# main.net
KiCad netlist of a schematic drawn in Altium Designer
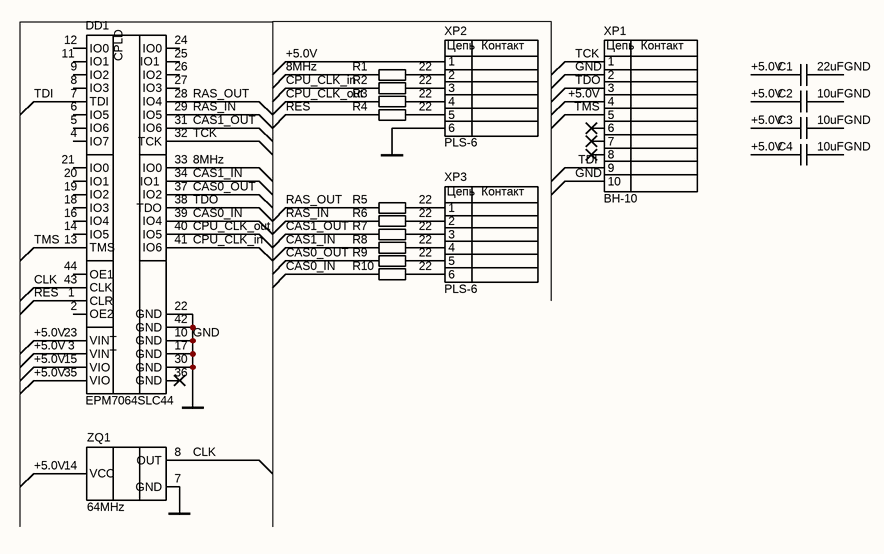
[diagram p0: main.SchDoc]

(export (version "E")
  (design (tool "Eeschema 10.0.6"))
  (components
    (comp (ref "C1") (value "22uF") (footprint "С1206") (libsource (lib "Capacitors") (part "CapCer")))
    (comp (ref "C2") (value "10uF") (footprint "C0805") (libsource (lib "Capacitors") (part "CapCer")))
    (comp (ref "C3") (value "10uF") (footprint "C0805") (libsource (lib "Capacitors") (part "CapCer")))
    (comp (ref "C4") (value "10uF") (footprint "C0805") (libsource (lib "Capacitors") (part "CapCer")))
    (comp (ref "DD1")
      (value "EPM7064SLC44")
      (footprint "PLCC-44-R")
      (description "44-Pin PLCC44")
      (libsource (lib "cpld") (part "EPM7064SLC44"))
    )
    (comp (ref "R1")
      (value "22")
      (footprint "R0603")
      (description "22 Ом 0603")
      (libsource (lib "Resistors") (part "Res"))
    )
    (comp (ref "R2")
      (value "22")
      (footprint "R0603")
      (description "22 Ом 0603")
      (libsource (lib "Resistors") (part "Res"))
    )
    (comp (ref "R3")
      (value "22")
      (footprint "R0603")
      (description "22 Ом 0603")
      (libsource (lib "Resistors") (part "Res"))
    )
    (comp (ref "R4")
      (value "22")
      (footprint "R0603")
      (description "22 Ом 0603")
      (libsource (lib "Resistors") (part "Res"))
    )
    (comp (ref "R5")
      (value "22")
      (footprint "R0603")
      (description "22 Ом 0603")
      (libsource (lib "Resistors") (part "Res"))
    )
    (comp (ref "R6")
      (value "22")
      (footprint "R0603")
      (description "22 Ом 0603")
      (libsource (lib "Resistors") (part "Res"))
    )
    (comp (ref "R7")
      (value "22")
      (footprint "R0603")
      (description "22 Ом 0603")
      (libsource (lib "Resistors") (part "Res"))
    )
    (comp (ref "R8")
      (value "22")
      (footprint "R0603")
      (description "22 Ом 0603")
      (libsource (lib "Resistors") (part "Res"))
    )
    (comp (ref "R9")
      (value "22")
      (footprint "R0603")
      (description "22 Ом 0603")
      (libsource (lib "Resistors") (part "Res"))
    )
    (comp (ref "R10")
      (value "22")
      (footprint "R0603")
      (description "22 Ом 0603")
      (libsource (lib "Resistors") (part "Res"))
    )
    (comp (ref "XP1")
      (value "BH-10")
      (footprint "BH-10")
      (description "10 Position Total Dual Row 2.54 mm Pitch Straight Male Shrouded Box Header")
      (fields (field (name "MF") "Sullins Connector") (field (name "MP") "SBH11-PBPC-D05-ST-BK"))
      (libsource (lib "Connectors") (part "BH-10"))
    )
    (comp (ref "XP2") (value "PLS-6") (footprint "6pin") (libsource (lib "Connectors") (part "PLS-6")))
    (comp (ref "XP3") (value "PLS-6") (footprint "6pin") (libsource (lib "Connectors") (part "PLS-6")))
    (comp (ref "ZQ1")
      (value "64MHz")
      (footprint "OSC_ECS-100A-240")
      (description "Oscillator  14-DIP, 4 Leads (Full Size, Metal Can)")
      (fields (field (name "MP") "ECS-100A-240"))
      (libsource (lib "Oscillators") (part "KXO-240"))
    )
  )
  (nets
    (net (code "1") (name "/+5.0V") (class "Default")
      (node (ref "C1") (pin "1") (pinfunction "1_1") (pintype "passive"))
      (node (ref "C2") (pin "1") (pinfunction "1_1") (pintype "passive"))
      (node (ref "C3") (pin "1") (pinfunction "1_1") (pintype "passive"))
      (node (ref "C4") (pin "1") (pinfunction "1_1") (pintype "passive"))
      (node (ref "DD1") (pin "15") (pinfunction "VIO_15") (pintype "passive"))
      (node (ref "DD1") (pin "23") (pinfunction "VINT_23") (pintype "passive"))
      (node (ref "DD1") (pin "3") (pinfunction "VINT_3") (pintype "passive"))
      (node (ref "DD1") (pin "35") (pinfunction "VIO_35") (pintype "passive"))
      (node (ref "XP1") (pin "4") (pinfunction "4_4") (pintype "passive"))
      (node (ref "XP2") (pin "1") (pinfunction "1_1") (pintype "passive"))
      (node (ref "ZQ1") (pin "14") (pinfunction "VCC_14") (pintype "passive"))
    )
    (net (code "2") (name "/8MHz") (class "Default")
      (node (ref "DD1") (pin "33") (pinfunction "IO0_33") (pintype "passive"))
      (node (ref "R1") (pin "1") (pinfunction "1_1") (pintype "passive"))
    )
    (net (code "3") (name "/CAS0_IN") (class "Default")
      (node (ref "DD1") (pin "39") (pinfunction "IO4_39") (pintype "passive"))
      (node (ref "R10") (pin "1") (pinfunction "1_1") (pintype "passive"))
    )
    (net (code "4") (name "/CAS0_OUT") (class "Default")
      (node (ref "DD1") (pin "37") (pinfunction "IO2_37") (pintype "passive"))
      (node (ref "R9") (pin "1") (pinfunction "1_1") (pintype "passive"))
    )
    (net (code "5") (name "/CAS1_IN") (class "Default")
      (node (ref "DD1") (pin "34") (pinfunction "IO1_34") (pintype "passive"))
      (node (ref "R8") (pin "1") (pinfunction "1_1") (pintype "passive"))
    )
    (net (code "6") (name "/CAS1_OUT") (class "Default")
      (node (ref "DD1") (pin "31") (pinfunction "IO6_31") (pintype "passive"))
      (node (ref "R7") (pin "1") (pinfunction "1_1") (pintype "passive"))
    )
    (net (code "7") (name "/CLK") (class "Default")
      (node (ref "DD1") (pin "43") (pinfunction "CLK_43") (pintype "passive"))
      (node (ref "ZQ1") (pin "8") (pinfunction "OUT_8") (pintype "passive"))
    )
    (net (code "8") (name "/CPU_CLK_in") (class "Default")
      (node (ref "DD1") (pin "41") (pinfunction "IO6_41") (pintype "passive"))
      (node (ref "R2") (pin "1") (pinfunction "1_1") (pintype "passive"))
    )
    (net (code "9") (name "/CPU_CLK_out") (class "Default")
      (node (ref "DD1") (pin "40") (pinfunction "IO5_40") (pintype "passive"))
      (node (ref "R3") (pin "1") (pinfunction "1_1") (pintype "passive"))
    )
    (net (code "10") (name "/RAS_IN") (class "Default")
      (node (ref "DD1") (pin "29") (pinfunction "IO5_29") (pintype "passive"))
      (node (ref "R6") (pin "1") (pinfunction "1_1") (pintype "passive"))
    )
    (net (code "11") (name "/RAS_OUT") (class "Default")
      (node (ref "DD1") (pin "28") (pinfunction "IO4_28") (pintype "passive"))
      (node (ref "R5") (pin "1") (pinfunction "1_1") (pintype "passive"))
    )
    (net (code "12") (name "/RES") (class "Default")
      (node (ref "DD1") (pin "1") (pinfunction "CLR_1") (pintype "passive"))
      (node (ref "R4") (pin "1") (pinfunction "1_1") (pintype "passive"))
    )
    (net (code "13") (name "/TCK") (class "Default")
      (node (ref "DD1") (pin "32") (pinfunction "TCK_32") (pintype "passive"))
      (node (ref "XP1") (pin "1") (pinfunction "1_1") (pintype "passive"))
    )
    (net (code "14") (name "/TDI") (class "Default")
      (node (ref "DD1") (pin "7") (pinfunction "TDI_7") (pintype "passive"))
      (node (ref "XP1") (pin "9") (pinfunction "9_9") (pintype "passive"))
    )
    (net (code "15") (name "/TDO") (class "Default")
      (node (ref "DD1") (pin "38") (pinfunction "TDO_38") (pintype "passive"))
      (node (ref "XP1") (pin "3") (pinfunction "3_3") (pintype "passive"))
    )
    (net (code "16") (name "/TMS") (class "Default")
      (node (ref "DD1") (pin "13") (pinfunction "TMS_13") (pintype "passive"))
      (node (ref "XP1") (pin "5") (pinfunction "5_5") (pintype "passive"))
    )
    (net (code "17") (name "GND") (class "Default")
      (node (ref "C1") (pin "2") (pinfunction "2_2") (pintype "passive"))
      (node (ref "C2") (pin "2") (pinfunction "2_2") (pintype "passive"))
      (node (ref "C3") (pin "2") (pinfunction "2_2") (pintype "passive"))
      (node (ref "C4") (pin "2") (pinfunction "2_2") (pintype "passive"))
      (node (ref "DD1") (pin "10") (pinfunction "GND_10") (pintype "passive"))
      (node (ref "DD1") (pin "17") (pinfunction "GND_17") (pintype "passive"))
      (node (ref "DD1") (pin "22") (pinfunction "GND_22") (pintype "passive"))
      (node (ref "DD1") (pin "30") (pinfunction "GND_30") (pintype "passive"))
      (node (ref "DD1") (pin "42") (pinfunction "GND_42") (pintype "passive"))
      (node (ref "XP1") (pin "10") (pinfunction "10_10") (pintype "passive"))
      (node (ref "XP1") (pin "2") (pinfunction "2_2") (pintype "passive"))
      (node (ref "XP2") (pin "6") (pinfunction "6_6") (pintype "passive"))
      (node (ref "ZQ1") (pin "7") (pinfunction "GND_7") (pintype "passive"))
    )
    (net (code "18") (name "Net-(R1-Pad2)") (class "Default")
      (node (ref "R1") (pin "2") (pinfunction "2_2") (pintype "passive"))
      (node (ref "XP2") (pin "2") (pinfunction "2_2") (pintype "passive"))
    )
    (net (code "19") (name "Net-(R2-Pad2)") (class "Default")
      (node (ref "R2") (pin "2") (pinfunction "2_2") (pintype "passive"))
      (node (ref "XP2") (pin "3") (pinfunction "3_3") (pintype "passive"))
    )
    (net (code "20") (name "Net-(R3-Pad2)") (class "Default")
      (node (ref "R3") (pin "2") (pinfunction "2_2") (pintype "passive"))
      (node (ref "XP2") (pin "4") (pinfunction "4_4") (pintype "passive"))
    )
    (net (code "21") (name "Net-(R4-Pad2)") (class "Default")
      (node (ref "R4") (pin "2") (pinfunction "2_2") (pintype "passive"))
      (node (ref "XP2") (pin "5") (pinfunction "5_5") (pintype "passive"))
    )
    (net (code "22") (name "Net-(R5-Pad2)") (class "Default")
      (node (ref "R5") (pin "2") (pinfunction "2_2") (pintype "passive"))
      (node (ref "XP3") (pin "1") (pinfunction "1_1") (pintype "passive"))
    )
    (net (code "23") (name "Net-(R6-Pad2)") (class "Default")
      (node (ref "R6") (pin "2") (pinfunction "2_2") (pintype "passive"))
      (node (ref "XP3") (pin "2") (pinfunction "2_2") (pintype "passive"))
    )
    (net (code "24") (name "Net-(R7-Pad2)") (class "Default")
      (node (ref "R7") (pin "2") (pinfunction "2_2") (pintype "passive"))
      (node (ref "XP3") (pin "3") (pinfunction "3_3") (pintype "passive"))
    )
    (net (code "25") (name "Net-(R8-Pad2)") (class "Default")
      (node (ref "R8") (pin "2") (pinfunction "2_2") (pintype "passive"))
      (node (ref "XP3") (pin "4") (pinfunction "4_4") (pintype "passive"))
    )
    (net (code "26") (name "Net-(R9-Pad2)") (class "Default")
      (node (ref "R9") (pin "2") (pinfunction "2_2") (pintype "passive"))
      (node (ref "XP3") (pin "5") (pinfunction "5_5") (pintype "passive"))
    )
    (net (code "27") (name "Net-(R10-Pad2)") (class "Default")
      (node (ref "R10") (pin "2") (pinfunction "2_2") (pintype "passive"))
      (node (ref "XP3") (pin "6") (pinfunction "6_6") (pintype "passive"))
    )
    (net (code "28") (name "unconnected-(DD1-GND-Pad36)") (class "Default")
      (node (ref "DD1") (pin "36") (pinfunction "GND_36") (pintype "passive+no_connect"))
    )
    (net (code "29") (name "unconnected-(DD1-IO0-Pad12)") (class "Default")
      (node (ref "DD1") (pin "12") (pinfunction "IO0_12") (pintype "passive"))
    )
    (net (code "30") (name "unconnected-(DD1-IO0-Pad21)") (class "Default")
      (node (ref "DD1") (pin "21") (pinfunction "IO0_21") (pintype "passive"))
    )
    (net (code "31") (name "unconnected-(DD1-IO0-Pad24)") (class "Default")
      (node (ref "DD1") (pin "24") (pinfunction "IO0_24") (pintype "passive"))
    )
    (net (code "32") (name "unconnected-(DD1-IO1-Pad11)") (class "Default")
      (node (ref "DD1") (pin "11") (pinfunction "IO1_11") (pintype "passive"))
    )
    (net (code "33") (name "unconnected-(DD1-IO1-Pad20)") (class "Default")
      (node (ref "DD1") (pin "20") (pinfunction "IO1_20") (pintype "passive"))
    )
    (net (code "34") (name "unconnected-(DD1-IO1-Pad25)") (class "Default")
      (node (ref "DD1") (pin "25") (pinfunction "IO1_25") (pintype "passive"))
    )
    (net (code "35") (name "unconnected-(DD1-IO2-Pad9)") (class "Default")
      (node (ref "DD1") (pin "9") (pinfunction "IO2_9") (pintype "passive"))
    )
    (net (code "36") (name "unconnected-(DD1-IO2-Pad19)") (class "Default")
      (node (ref "DD1") (pin "19") (pinfunction "IO2_19") (pintype "passive"))
    )
    (net (code "37") (name "unconnected-(DD1-IO2-Pad26)") (class "Default")
      (node (ref "DD1") (pin "26") (pinfunction "IO2_26") (pintype "passive"))
    )
    (net (code "38") (name "unconnected-(DD1-IO3-Pad8)") (class "Default")
      (node (ref "DD1") (pin "8") (pinfunction "IO3_8") (pintype "passive"))
    )
    (net (code "39") (name "unconnected-(DD1-IO3-Pad18)") (class "Default")
      (node (ref "DD1") (pin "18") (pinfunction "IO3_18") (pintype "passive"))
    )
    (net (code "40") (name "unconnected-(DD1-IO3-Pad27)") (class "Default")
      (node (ref "DD1") (pin "27") (pinfunction "IO3_27") (pintype "passive"))
    )
    (net (code "41") (name "unconnected-(DD1-IO4-Pad16)") (class "Default")
      (node (ref "DD1") (pin "16") (pinfunction "IO4_16") (pintype "passive"))
    )
    (net (code "42") (name "unconnected-(DD1-IO5-Pad6)") (class "Default")
      (node (ref "DD1") (pin "6") (pinfunction "IO5_6") (pintype "passive"))
    )
    (net (code "43") (name "unconnected-(DD1-IO5-Pad14)") (class "Default")
      (node (ref "DD1") (pin "14") (pinfunction "IO5_14") (pintype "passive"))
    )
    (net (code "44") (name "unconnected-(DD1-IO6-Pad5)") (class "Default")
      (node (ref "DD1") (pin "5") (pinfunction "IO6_5") (pintype "passive"))
    )
    (net (code "45") (name "unconnected-(DD1-IO7-Pad4)") (class "Default")
      (node (ref "DD1") (pin "4") (pinfunction "IO7_4") (pintype "passive"))
    )
    (net (code "46") (name "unconnected-(DD1-OE1-Pad44)") (class "Default")
      (node (ref "DD1") (pin "44") (pinfunction "OE1_44") (pintype "passive"))
    )
    (net (code "47") (name "unconnected-(DD1-OE2-Pad2)") (class "Default")
      (node (ref "DD1") (pin "2") (pinfunction "OE2_2") (pintype "passive"))
    )
    (net (code "48") (name "unconnected-(XP1-Pad6)") (class "Default")
      (node (ref "XP1") (pin "6") (pinfunction "6_6") (pintype "passive+no_connect"))
    )
    (net (code "49") (name "unconnected-(XP1-Pad7)") (class "Default")
      (node (ref "XP1") (pin "7") (pinfunction "7_7") (pintype "passive+no_connect"))
    )
    (net (code "50") (name "unconnected-(XP1-Pad8)") (class "Default")
      (node (ref "XP1") (pin "8") (pinfunction "8_8") (pintype "passive+no_connect"))
    )
  )
)
